# untitled.net
KiCad netlist of a schematic drawn in EAGLE
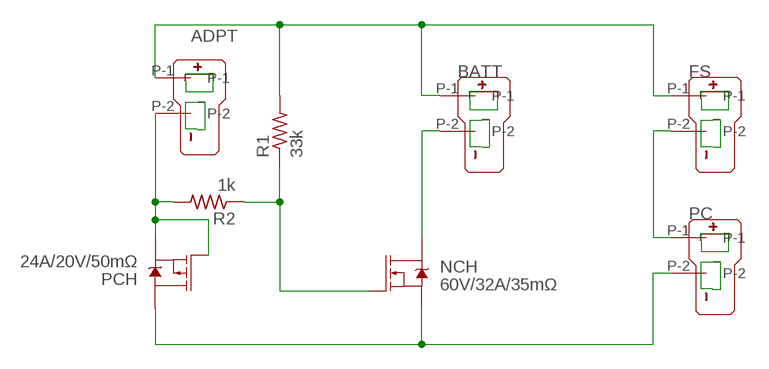
[diagram p0: schematic, sheet 1]

(export (version "E")
  (design (tool "Eeschema 10.0.6"))
  (components
    (comp (ref "ADPT")
      (value "T-PLUG_CONNECTOR")
      (footprint "eagle-import:T_PLUG_CONNECTOR")
      (libsource (lib "eagle-import") (part "T-PLUG_CONNECTOR"))
    )
    (comp (ref "BATT")
      (value "T-PLUG_CONNECTOR")
      (footprint "eagle-import:T_PLUG_CONNECTOR")
      (libsource (lib "eagle-import") (part "T-PLUG_CONNECTOR"))
    )
    (comp (ref "FS")
      (value "T-PLUG_CONNECTOR")
      (footprint "eagle-import:T_PLUG_CONNECTOR")
      (libsource (lib "eagle-import") (part "T-PLUG_CONNECTOR"))
    )
    (comp (ref "NCH")
      (value "60V/32A/35mΩ")
      (footprint "eagle-import:TO220V")
      (libsource (lib "eagle-import") (part "MOSFET-NCH-FQP30N06L"))
    )
    (comp (ref "PC")
      (value "T-PLUG_CONNECTOR")
      (footprint "eagle-import:T_PLUG_CONNECTOR")
      (libsource (lib "eagle-import") (part "T-PLUG_CONNECTOR"))
    )
    (comp (ref "PCH")
      (value "24A/20V/50mΩ")
      (footprint "eagle-import:TO220V")
      (libsource (lib "eagle-import") (part "MOSFET_PCH-NDP6020P"))
    )
    (comp (ref "R1")
      (value "33k")
      (footprint "eagle-import:0411_15")
      (libsource (lib "eagle-import") (part "R-US_0411/15"))
    )
    (comp (ref "R2")
      (value "1k")
      (footprint "eagle-import:0411_15")
      (libsource (lib "eagle-import") (part "R-US_0411/15"))
    )
  )
  (nets
    (net (code "1") (name "Net-(ADPT-PadP-1)") (class "Default")
      (node (ref "ADPT") (pin "P-1") (pinfunction "P-1_P-1") (pintype "passive"))
      (node (ref "BATT") (pin "P-1") (pinfunction "P-1_P-1") (pintype "passive"))
      (node (ref "FS") (pin "P-1") (pinfunction "P-1_P-1") (pintype "passive"))
      (node (ref "R1") (pin "2") (pinfunction "2_2") (pintype "passive"))
    )
    (net (code "2") (name "Net-(FS-PadP-2)") (class "Default")
      (node (ref "FS") (pin "P-2") (pinfunction "P-2_P-2") (pintype "passive"))
      (node (ref "PC") (pin "P-1") (pinfunction "P-1_P-1") (pintype "passive"))
    )
    (net (code "3") (name "Net-(NCH-D)") (class "Default")
      (node (ref "BATT") (pin "P-2") (pinfunction "P-2_P-2") (pintype "passive"))
      (node (ref "NCH") (pin "2") (pinfunction "D_2") (pintype "bidirectional"))
    )
    (net (code "4") (name "Net-(NCH-G)") (class "Default")
      (node (ref "NCH") (pin "1") (pinfunction "G_1") (pintype "bidirectional"))
      (node (ref "R1") (pin "1") (pinfunction "1_1") (pintype "passive"))
      (node (ref "R2") (pin "1") (pinfunction "1_1") (pintype "passive"))
    )
    (net (code "5") (name "Net-(NCH-S)") (class "Default")
      (node (ref "NCH") (pin "3") (pinfunction "S_3") (pintype "bidirectional"))
      (node (ref "PC") (pin "P-2") (pinfunction "P-2_P-2") (pintype "passive"))
      (node (ref "PCH") (pin "2") (pinfunction "D_2") (pintype "bidirectional"))
    )
    (net (code "6") (name "Net-(PCH-G)") (class "Default")
      (node (ref "ADPT") (pin "P-2") (pinfunction "P-2_P-2") (pintype "passive"))
      (node (ref "PCH") (pin "1") (pinfunction "G_1") (pintype "bidirectional"))
      (node (ref "PCH") (pin "3") (pinfunction "S_3") (pintype "bidirectional"))
      (node (ref "R2") (pin "2") (pinfunction "2_2") (pintype "passive"))
    )
  )
)
